# Wireless_Weather_Station.net
KiCad netlist of a schematic drawn in Altium Designer
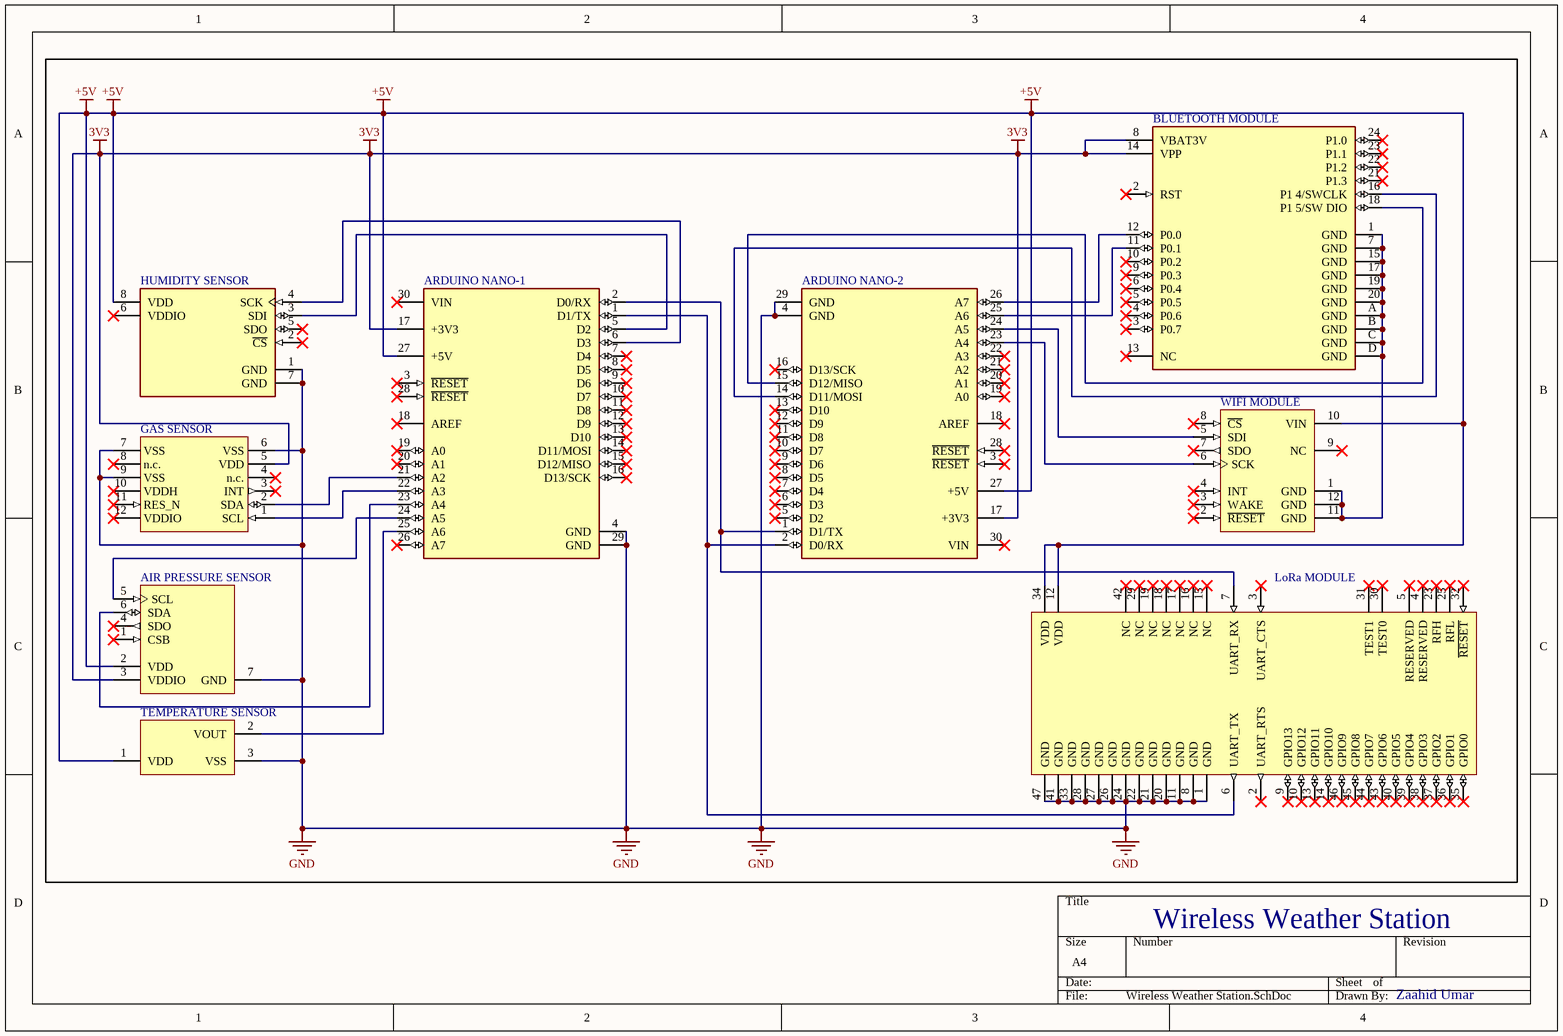
[diagram p0: Wireless Weather Station.SchDoc]

(export (version "E")
  (design (tool "Eeschema 10.0.6"))
  (components
    (comp (ref "AIR PRESSURE SENSOR")
      (value "BMP180")
      (footprint "BOSC-BMP180-7_V")
      (description "Digital Pressure Sensor, 1.8 to 3.6 V, -40 to 85 degC, 7-Pin LGA, RoHS")
      (fields (field (name "MANUFACTURER") "Bosch Sensortec"))
      (libsource (lib "Altium Content Vault") (part "BOSC-BMP180-7"))
    )
    (comp (ref "ARDUINO NANO-1")
      (value "A000005")
      (footprint "FP-A000005-MFG")
      (description "ARDUINO NANO ATMEGA328 EVAL BRD")
      (libsource (lib "Altium Content Vault") (part "d190c066e99afd1c6882cf92e11b2cc"))
    )
    (comp (ref "ARDUINO NANO-2")
      (value "A000005")
      (footprint "FP-A000005-MFG")
      (description "ARDUINO NANO ATMEGA328 EVAL BRD")
      (libsource (lib "") (part "d190c066e99afd1c6882cf92e11b2cc_1"))
    )
    (comp (ref "BLUETOOTH MODULE")
      (value "ENW-89846A1KF")
      (footprint "FP-ENW-89846A1KF-MFG")
      (description "RF TXRX MOD BLUETOOTH CHIP ANT")
      (fields
        (field (name "MANUFACTURER") "Panasonic")
        (field (name "OCTOPART") "https://octopart.com/enw-89846a1kf-panasonic-38566823")
      )
      (libsource (lib "Altium Content Vault") (part "e19c780454142849fd90e01d0101f89"))
    )
    (comp (ref "GAS SENSOR")
      (value "ZMOD4510AI1V")
      (footprint "ZMODxxxx 12 Leads- LGG12")
      (description "ZMOD4510AI1V ZMOD4510 Series 3.6 V 11 mA Gas Sensor Module for Outdoor Air Quality - LGA-12")
      (libsource (lib "Altium Content Vault") (part "ZMOD4510AI1V"))
    )
    (comp (ref "HUMIDITY SENSOR")
      (value "BME280")
      (footprint "FP-BME280-MFG")
      (description "SENSOR PRESSURE HUMIDITY TEMP")
      (libsource (lib "Altium Content Vault") (part "d58e2f6669bc67e6a2bc6a28610ca79"))
    )
    (comp (ref "LoRa MODULE")
      (value "RN2483-I/RM095")
      (footprint "MCHP-RN2483-47_V")
      (fields (field (name "MANUFACTURER") "Microchip"))
      (libsource (lib "Altium Content Vault") (part "MCHP-RN2483-IRM095-47"))
    )
    (comp (ref "TEMPERATURE SENSOR")
      (value "TC1047AVNBTR")
      (footprint "SOT-23-NB3_L")
      (description "Precision Temperature-to-Voltage Converter, 3-Pin SOT-23, Extended Temperature, Tape and Reel")
      (libsource (lib "Altium Content Vault") (part "CON-TVC-TC1046-3"))
    )
    (comp (ref "WIFI MODULE")
      (value "MRF24J40MA-I/RM")
      (footprint "MRF24J40MA")
      (description "2.4 GHz IEEE Std. 802.15.4, RF Transceiver 12-Pin Module, Industrial Temperature")
      (libsource (lib "Altium Content Vault") (part "RF-TRX-MRF24J40-IL12"))
    )
  )
  (nets
    (net (code "1") (name "+5V") (class "Default")
      (node (ref "AIR PRESSURE SENSOR") (pin "2") (pinfunction "VDD_2") (pintype "power_in"))
      (node (ref "ARDUINO NANO-1") (pin "27") (pinfunction "+5V_27") (pintype "power_in"))
      (node (ref "ARDUINO NANO-2") (pin "27") (pinfunction "+5V_27") (pintype "power_in"))
      (node (ref "HUMIDITY SENSOR") (pin "8") (pinfunction "VDD_8") (pintype "power_in"))
      (node (ref "LoRa MODULE") (pin "12") (pinfunction "VDD_12") (pintype "power_in"))
      (node (ref "LoRa MODULE") (pin "34") (pinfunction "VDD_34") (pintype "power_in"))
      (node (ref "TEMPERATURE SENSOR") (pin "1") (pinfunction "VDD_1") (pintype "power_in"))
      (node (ref "WIFI MODULE") (pin "10") (pinfunction "VIN_10") (pintype "power_in"))
    )
    (net (code "2") (name "3V3") (class "Default")
      (node (ref "AIR PRESSURE SENSOR") (pin "3") (pinfunction "VDDIO_3") (pintype "power_in"))
      (node (ref "ARDUINO NANO-1") (pin "17") (pinfunction "+3V3_17") (pintype "power_in"))
      (node (ref "ARDUINO NANO-2") (pin "17") (pinfunction "+3V3_17") (pintype "power_in"))
      (node (ref "BLUETOOTH MODULE") (pin "14") (pinfunction "VPP_14") (pintype "power_in"))
      (node (ref "BLUETOOTH MODULE") (pin "8") (pinfunction "VBAT3V_8") (pintype "power_in"))
      (node (ref "GAS SENSOR") (pin "5") (pinfunction "VDD_5") (pintype "power_in"))
    )
    (net (code "3") (name "GND") (class "Default")
      (node (ref "AIR PRESSURE SENSOR") (pin "7") (pinfunction "GND_7") (pintype "power_in"))
      (node (ref "ARDUINO NANO-1") (pin "29") (pinfunction "GND_29") (pintype "power_in"))
      (node (ref "ARDUINO NANO-1") (pin "4") (pinfunction "GND_4") (pintype "power_in"))
      (node (ref "ARDUINO NANO-2") (pin "29") (pinfunction "GND_29") (pintype "power_in"))
      (node (ref "ARDUINO NANO-2") (pin "4") (pinfunction "GND_4") (pintype "power_in"))
      (node (ref "GAS SENSOR") (pin "6") (pinfunction "VSS_6") (pintype "power_in"))
      (node (ref "GAS SENSOR") (pin "7") (pinfunction "VSS_7") (pintype "power_in"))
      (node (ref "GAS SENSOR") (pin "9") (pinfunction "VSS_9") (pintype "power_in"))
      (node (ref "HUMIDITY SENSOR") (pin "1") (pinfunction "GND_1") (pintype "power_in"))
      (node (ref "HUMIDITY SENSOR") (pin "7") (pinfunction "GND_7") (pintype "power_in"))
      (node (ref "LoRa MODULE") (pin "1") (pinfunction "GND_1") (pintype "power_in"))
      (node (ref "LoRa MODULE") (pin "11") (pinfunction "GND_11") (pintype "power_in"))
      (node (ref "LoRa MODULE") (pin "20") (pinfunction "GND_20") (pintype "power_in"))
      (node (ref "LoRa MODULE") (pin "21") (pinfunction "GND_21") (pintype "power_in"))
      (node (ref "LoRa MODULE") (pin "22") (pinfunction "GND_22") (pintype "power_in"))
      (node (ref "LoRa MODULE") (pin "24") (pinfunction "GND_24") (pintype "power_in"))
      (node (ref "LoRa MODULE") (pin "26") (pinfunction "GND_26") (pintype "power_in"))
      (node (ref "LoRa MODULE") (pin "27") (pinfunction "GND_27") (pintype "power_in"))
      (node (ref "LoRa MODULE") (pin "28") (pinfunction "GND_28") (pintype "power_in"))
      (node (ref "LoRa MODULE") (pin "33") (pinfunction "GND_33") (pintype "power_in"))
      (node (ref "LoRa MODULE") (pin "41") (pinfunction "GND_41") (pintype "power_in"))
      (node (ref "LoRa MODULE") (pin "47") (pinfunction "GND_47") (pintype "power_in"))
      (node (ref "LoRa MODULE") (pin "8") (pinfunction "GND_8") (pintype "power_in"))
      (node (ref "TEMPERATURE SENSOR") (pin "3") (pinfunction "VSS_3") (pintype "power_in"))
    )
    (net (code "4") (name "Net-(AIR PRESSURE SENSOR-SCL)") (class "Default")
      (node (ref "AIR PRESSURE SENSOR") (pin "5") (pinfunction "SCL_5") (pintype "input"))
      (node (ref "ARDUINO NANO-1") (pin "24") (pinfunction "A5_24") (pintype "bidirectional"))
    )
    (net (code "5") (name "Net-(AIR PRESSURE SENSOR-SDA)") (class "Default")
      (node (ref "AIR PRESSURE SENSOR") (pin "6") (pinfunction "SDA_6") (pintype "bidirectional"))
      (node (ref "ARDUINO NANO-1") (pin "23") (pinfunction "A4_23") (pintype "bidirectional"))
    )
    (net (code "6") (name "Net-(ARDUINO NANO-1-A2)") (class "Default")
      (node (ref "ARDUINO NANO-1") (pin "21") (pinfunction "A2_21") (pintype "bidirectional"))
      (node (ref "GAS SENSOR") (pin "2") (pinfunction "SDA_2") (pintype "bidirectional"))
    )
    (net (code "7") (name "Net-(ARDUINO NANO-1-A3)") (class "Default")
      (node (ref "ARDUINO NANO-1") (pin "22") (pinfunction "A3_22") (pintype "bidirectional"))
      (node (ref "GAS SENSOR") (pin "1") (pinfunction "SCL_1") (pintype "input"))
    )
    (net (code "8") (name "Net-(ARDUINO NANO-1-A6)") (class "Default")
      (node (ref "ARDUINO NANO-1") (pin "25") (pinfunction "A6_25") (pintype "bidirectional"))
      (node (ref "TEMPERATURE SENSOR") (pin "2") (pinfunction "VOUT_2") (pintype "power_in"))
    )
    (net (code "9") (name "Net-(ARDUINO NANO-1-D0{slash}RX)") (class "Default")
      (node (ref "ARDUINO NANO-1") (pin "2") (pinfunction "D0/RX_2") (pintype "bidirectional"))
      (node (ref "ARDUINO NANO-2") (pin "1") (pinfunction "D1/TX_1") (pintype "bidirectional"))
      (node (ref "LoRa MODULE") (pin "7") (pinfunction "UART_RX_7") (pintype "input"))
    )
    (net (code "10") (name "Net-(ARDUINO NANO-1-D1{slash}TX)") (class "Default")
      (node (ref "ARDUINO NANO-1") (pin "1") (pinfunction "D1/TX_1") (pintype "bidirectional"))
      (node (ref "ARDUINO NANO-2") (pin "2") (pinfunction "D0/RX_2") (pintype "bidirectional"))
      (node (ref "LoRa MODULE") (pin "6") (pinfunction "UART_TX_6") (pintype "output"))
    )
    (net (code "11") (name "Net-(ARDUINO NANO-1-D2)") (class "Default")
      (node (ref "ARDUINO NANO-1") (pin "5") (pinfunction "D2_5") (pintype "bidirectional"))
      (node (ref "HUMIDITY SENSOR") (pin "3") (pinfunction "SDI_3") (pintype "bidirectional"))
    )
    (net (code "12") (name "Net-(ARDUINO NANO-1-D3)") (class "Default")
      (node (ref "ARDUINO NANO-1") (pin "6") (pinfunction "D3_6") (pintype "bidirectional"))
      (node (ref "HUMIDITY SENSOR") (pin "4") (pinfunction "SCK_4") (pintype "input"))
    )
    (net (code "13") (name "Net-(ARDUINO NANO-2-A4)") (class "Default")
      (node (ref "ARDUINO NANO-2") (pin "23") (pinfunction "A4_23") (pintype "bidirectional"))
      (node (ref "WIFI MODULE") (pin "6") (pinfunction "SCK_6") (pintype "input"))
    )
    (net (code "14") (name "Net-(ARDUINO NANO-2-A5)") (class "Default")
      (node (ref "ARDUINO NANO-2") (pin "24") (pinfunction "A5_24") (pintype "bidirectional"))
      (node (ref "WIFI MODULE") (pin "5") (pinfunction "SDI_5") (pintype "input"))
    )
    (net (code "15") (name "Net-(ARDUINO NANO-2-A6)") (class "Default")
      (node (ref "ARDUINO NANO-2") (pin "25") (pinfunction "A6_25") (pintype "bidirectional"))
      (node (ref "BLUETOOTH MODULE") (pin "11") (pinfunction "P0.1_11") (pintype "bidirectional"))
    )
    (net (code "16") (name "Net-(ARDUINO NANO-2-A7)") (class "Default")
      (node (ref "ARDUINO NANO-2") (pin "26") (pinfunction "A7_26") (pintype "bidirectional"))
      (node (ref "BLUETOOTH MODULE") (pin "12") (pinfunction "P0.0_12") (pintype "bidirectional"))
    )
    (net (code "17") (name "Net-(ARDUINO NANO-2-D11{slash}MOSI)") (class "Default")
      (node (ref "ARDUINO NANO-2") (pin "14") (pinfunction "D11/MOSI_14") (pintype "bidirectional"))
      (node (ref "BLUETOOTH MODULE") (pin "16") (pinfunction "P1_4/SWCLK_16") (pintype "bidirectional"))
    )
    (net (code "18") (name "Net-(ARDUINO NANO-2-D12{slash}MISO)") (class "Default")
      (node (ref "ARDUINO NANO-2") (pin "15") (pinfunction "D12/MISO_15") (pintype "bidirectional"))
      (node (ref "BLUETOOTH MODULE") (pin "18") (pinfunction "P1_5/SW_DIO_18") (pintype "bidirectional"))
    )
    (net (code "19") (name "Net-(BLUETOOTH MODULE-GND-Pad1)") (class "Default")
      (node (ref "BLUETOOTH MODULE") (pin "1") (pinfunction "GND_1") (pintype "power_in"))
      (node (ref "BLUETOOTH MODULE") (pin "15") (pinfunction "GND_15") (pintype "power_in"))
      (node (ref "BLUETOOTH MODULE") (pin "17") (pinfunction "GND_17") (pintype "power_in"))
      (node (ref "BLUETOOTH MODULE") (pin "19") (pinfunction "GND_19") (pintype "power_in"))
      (node (ref "BLUETOOTH MODULE") (pin "20") (pinfunction "GND_20") (pintype "power_in"))
      (node (ref "BLUETOOTH MODULE") (pin "7") (pinfunction "GND_7") (pintype "power_in"))
      (node (ref "BLUETOOTH MODULE") (pin "A") (pinfunction "GND_A") (pintype "power_in"))
      (node (ref "BLUETOOTH MODULE") (pin "B") (pinfunction "GND_B") (pintype "power_in"))
      (node (ref "BLUETOOTH MODULE") (pin "C") (pinfunction "GND_C") (pintype "power_in"))
      (node (ref "BLUETOOTH MODULE") (pin "D") (pinfunction "GND_D") (pintype "power_in"))
      (node (ref "WIFI MODULE") (pin "1") (pinfunction "GND_1") (pintype "power_in"))
      (node (ref "WIFI MODULE") (pin "11") (pinfunction "GND_11") (pintype "power_in"))
      (node (ref "WIFI MODULE") (pin "12") (pinfunction "GND_12") (pintype "power_in"))
    )
    (net (code "20") (name "unconnected-(AIR PRESSURE SENSOR-CSB-Pad1)") (class "Default")
      (node (ref "AIR PRESSURE SENSOR") (pin "1") (pinfunction "CSB_1") (pintype "input+no_connect"))
    )
    (net (code "21") (name "unconnected-(AIR PRESSURE SENSOR-SDO-Pad4)") (class "Default")
      (node (ref "AIR PRESSURE SENSOR") (pin "4") (pinfunction "SDO_4") (pintype "output+no_connect"))
    )
    (net (code "22") (name "unconnected-(ARDUINO NANO-1-A0-Pad19)") (class "Default")
      (node (ref "ARDUINO NANO-1") (pin "19") (pinfunction "A0_19") (pintype "bidirectional+no_connect"))
    )
    (net (code "23") (name "unconnected-(ARDUINO NANO-1-A1-Pad20)") (class "Default")
      (node (ref "ARDUINO NANO-1") (pin "20") (pinfunction "A1_20") (pintype "bidirectional+no_connect"))
    )
    (net (code "24") (name "unconnected-(ARDUINO NANO-1-A7-Pad26)") (class "Default")
      (node (ref "ARDUINO NANO-1") (pin "26") (pinfunction "A7_26") (pintype "bidirectional+no_connect"))
    )
    (net (code "25") (name "unconnected-(ARDUINO NANO-1-AREF-Pad18)") (class "Default")
      (node (ref "ARDUINO NANO-1") (pin "18") (pinfunction "AREF_18") (pintype "passive+no_connect"))
    )
    (net (code "26") (name "unconnected-(ARDUINO NANO-1-D4-Pad7)") (class "Default")
      (node (ref "ARDUINO NANO-1") (pin "7") (pinfunction "D4_7") (pintype "bidirectional+no_connect"))
    )
    (net (code "27") (name "unconnected-(ARDUINO NANO-1-D5-Pad8)") (class "Default")
      (node (ref "ARDUINO NANO-1") (pin "8") (pinfunction "D5_8") (pintype "bidirectional+no_connect"))
    )
    (net (code "28") (name "unconnected-(ARDUINO NANO-1-D6-Pad9)") (class "Default")
      (node (ref "ARDUINO NANO-1") (pin "9") (pinfunction "D6_9") (pintype "bidirectional+no_connect"))
    )
    (net (code "29") (name "unconnected-(ARDUINO NANO-1-D7-Pad10)") (class "Default")
      (node (ref "ARDUINO NANO-1") (pin "10") (pinfunction "D7_10") (pintype "bidirectional+no_connect"))
    )
    (net (code "30") (name "unconnected-(ARDUINO NANO-1-D8-Pad11)") (class "Default")
      (node (ref "ARDUINO NANO-1") (pin "11") (pinfunction "D8_11") (pintype "bidirectional+no_connect"))
    )
    (net (code "31") (name "unconnected-(ARDUINO NANO-1-D9-Pad12)") (class "Default")
      (node (ref "ARDUINO NANO-1") (pin "12") (pinfunction "D9_12") (pintype "bidirectional+no_connect"))
    )
    (net (code "32") (name "unconnected-(ARDUINO NANO-1-D10-Pad13)") (class "Default")
      (node (ref "ARDUINO NANO-1") (pin "13") (pinfunction "D10_13") (pintype "bidirectional+no_connect"))
    )
    (net (code "33") (name "unconnected-(ARDUINO NANO-1-D11{slash}MOSI-Pad14)") (class "Default")
      (node (ref "ARDUINO NANO-1") (pin "14") (pinfunction "D11/MOSI_14") (pintype "bidirectional+no_connect"))
    )
    (net (code "34") (name "unconnected-(ARDUINO NANO-1-D12{slash}MISO-Pad15)") (class "Default")
      (node (ref "ARDUINO NANO-1") (pin "15") (pinfunction "D12/MISO_15") (pintype "bidirectional+no_connect"))
    )
    (net (code "35") (name "unconnected-(ARDUINO NANO-1-D13{slash}SCK-Pad16)") (class "Default")
      (node (ref "ARDUINO NANO-1") (pin "16") (pinfunction "D13/SCK_16") (pintype "bidirectional+no_connect"))
    )
    (net (code "36") (name "unconnected-(ARDUINO NANO-1-VIN-Pad30)") (class "Default")
      (node (ref "ARDUINO NANO-1") (pin "30") (pinfunction "VIN_30") (pintype "power_in+no_connect"))
    )
    (net (code "37") (name "unconnected-(ARDUINO NANO-1-~{RESET}-Pad3)") (class "Default")
      (node (ref "ARDUINO NANO-1") (pin "3") (pinfunction "~{RESET}_3") (pintype "input+no_connect"))
    )
    (net (code "38") (name "unconnected-(ARDUINO NANO-1-~{RESET}-Pad28)") (class "Default")
      (node (ref "ARDUINO NANO-1") (pin "28") (pinfunction "~{RESET}_28") (pintype "input+no_connect"))
    )
    (net (code "39") (name "unconnected-(ARDUINO NANO-2-A0-Pad19)") (class "Default")
      (node (ref "ARDUINO NANO-2") (pin "19") (pinfunction "A0_19") (pintype "bidirectional+no_connect"))
    )
    (net (code "40") (name "unconnected-(ARDUINO NANO-2-A1-Pad20)") (class "Default")
      (node (ref "ARDUINO NANO-2") (pin "20") (pinfunction "A1_20") (pintype "bidirectional+no_connect"))
    )
    (net (code "41") (name "unconnected-(ARDUINO NANO-2-A2-Pad21)") (class "Default")
      (node (ref "ARDUINO NANO-2") (pin "21") (pinfunction "A2_21") (pintype "bidirectional+no_connect"))
    )
    (net (code "42") (name "unconnected-(ARDUINO NANO-2-A3-Pad22)") (class "Default")
      (node (ref "ARDUINO NANO-2") (pin "22") (pinfunction "A3_22") (pintype "bidirectional+no_connect"))
    )
    (net (code "43") (name "unconnected-(ARDUINO NANO-2-AREF-Pad18)") (class "Default")
      (node (ref "ARDUINO NANO-2") (pin "18") (pinfunction "AREF_18") (pintype "passive+no_connect"))
    )
    (net (code "44") (name "unconnected-(ARDUINO NANO-2-D2-Pad5)") (class "Default")
      (node (ref "ARDUINO NANO-2") (pin "5") (pinfunction "D2_5") (pintype "bidirectional+no_connect"))
    )
    (net (code "45") (name "unconnected-(ARDUINO NANO-2-D3-Pad6)") (class "Default")
      (node (ref "ARDUINO NANO-2") (pin "6") (pinfunction "D3_6") (pintype "bidirectional+no_connect"))
    )
    (net (code "46") (name "unconnected-(ARDUINO NANO-2-D4-Pad7)") (class "Default")
      (node (ref "ARDUINO NANO-2") (pin "7") (pinfunction "D4_7") (pintype "bidirectional+no_connect"))
    )
    (net (code "47") (name "unconnected-(ARDUINO NANO-2-D5-Pad8)") (class "Default")
      (node (ref "ARDUINO NANO-2") (pin "8") (pinfunction "D5_8") (pintype "bidirectional+no_connect"))
    )
    (net (code "48") (name "unconnected-(ARDUINO NANO-2-D6-Pad9)") (class "Default")
      (node (ref "ARDUINO NANO-2") (pin "9") (pinfunction "D6_9") (pintype "bidirectional+no_connect"))
    )
    (net (code "49") (name "unconnected-(ARDUINO NANO-2-D7-Pad10)") (class "Default")
      (node (ref "ARDUINO NANO-2") (pin "10") (pinfunction "D7_10") (pintype "bidirectional+no_connect"))
    )
    (net (code "50") (name "unconnected-(ARDUINO NANO-2-D8-Pad11)") (class "Default")
      (node (ref "ARDUINO NANO-2") (pin "11") (pinfunction "D8_11") (pintype "bidirectional+no_connect"))
    )
    (net (code "51") (name "unconnected-(ARDUINO NANO-2-D9-Pad12)") (class "Default")
      (node (ref "ARDUINO NANO-2") (pin "12") (pinfunction "D9_12") (pintype "bidirectional+no_connect"))
    )
    (net (code "52") (name "unconnected-(ARDUINO NANO-2-D10-Pad13)") (class "Default")
      (node (ref "ARDUINO NANO-2") (pin "13") (pinfunction "D10_13") (pintype "bidirectional+no_connect"))
    )
    (net (code "53") (name "unconnected-(ARDUINO NANO-2-D13{slash}SCK-Pad16)") (class "Default")
      (node (ref "ARDUINO NANO-2") (pin "16") (pinfunction "D13/SCK_16") (pintype "bidirectional+no_connect"))
    )
    (net (code "54") (name "unconnected-(ARDUINO NANO-2-VIN-Pad30)") (class "Default")
      (node (ref "ARDUINO NANO-2") (pin "30") (pinfunction "VIN_30") (pintype "power_in+no_connect"))
    )
    (net (code "55") (name "unconnected-(ARDUINO NANO-2-~{RESET}-Pad3)") (class "Default")
      (node (ref "ARDUINO NANO-2") (pin "3") (pinfunction "~{RESET}_3") (pintype "input+no_connect"))
    )
    (net (code "56") (name "unconnected-(ARDUINO NANO-2-~{RESET}-Pad28)") (class "Default")
      (node (ref "ARDUINO NANO-2") (pin "28") (pinfunction "~{RESET}_28") (pintype "input+no_connect"))
    )
    (net (code "57") (name "unconnected-(BLUETOOTH MODULE-NC-Pad13)") (class "Default")
      (node (ref "BLUETOOTH MODULE") (pin "13") (pinfunction "NC_13") (pintype "passive+no_connect"))
    )
    (net (code "58") (name "unconnected-(BLUETOOTH MODULE-P0.2-Pad10)") (class "Default")
      (node (ref "BLUETOOTH MODULE") (pin "10") (pinfunction "P0.2_10") (pintype "bidirectional+no_connect"))
    )
    (net (code "59") (name "unconnected-(BLUETOOTH MODULE-P0.3-Pad9)") (class "Default")
      (node (ref "BLUETOOTH MODULE") (pin "9") (pinfunction "P0.3_9") (pintype "bidirectional+no_connect"))
    )
    (net (code "60") (name "unconnected-(BLUETOOTH MODULE-P0.4-Pad6)") (class "Default")
      (node (ref "BLUETOOTH MODULE") (pin "6") (pinfunction "P0.4_6") (pintype "bidirectional+no_connect"))
    )
    (net (code "61") (name "unconnected-(BLUETOOTH MODULE-P0.5-Pad5)") (class "Default")
      (node (ref "BLUETOOTH MODULE") (pin "5") (pinfunction "P0.5_5") (pintype "bidirectional+no_connect"))
    )
    (net (code "62") (name "unconnected-(BLUETOOTH MODULE-P0.6-Pad4)") (class "Default")
      (node (ref "BLUETOOTH MODULE") (pin "4") (pinfunction "P0.6_4") (pintype "bidirectional+no_connect"))
    )
    (net (code "63") (name "unconnected-(BLUETOOTH MODULE-P0.7-Pad3)") (class "Default")
      (node (ref "BLUETOOTH MODULE") (pin "3") (pinfunction "P0.7_3") (pintype "bidirectional+no_connect"))
    )
    (net (code "64") (name "unconnected-(BLUETOOTH MODULE-P1.0-Pad24)") (class "Default")
      (node (ref "BLUETOOTH MODULE") (pin "24") (pinfunction "P1.0_24") (pintype "bidirectional+no_connect"))
    )
    (net (code "65") (name "unconnected-(BLUETOOTH MODULE-P1.1-Pad23)") (class "Default")
      (node (ref "BLUETOOTH MODULE") (pin "23") (pinfunction "P1.1_23") (pintype "bidirectional+no_connect"))
    )
    (net (code "66") (name "unconnected-(BLUETOOTH MODULE-P1.2-Pad22)") (class "Default")
      (node (ref "BLUETOOTH MODULE") (pin "22") (pinfunction "P1.2_22") (pintype "bidirectional+no_connect"))
    )
    (net (code "67") (name "unconnected-(BLUETOOTH MODULE-P1.3-Pad21)") (class "Default")
      (node (ref "BLUETOOTH MODULE") (pin "21") (pinfunction "P1.3_21") (pintype "bidirectional+no_connect"))
    )
    (net (code "68") (name "unconnected-(BLUETOOTH MODULE-RST-Pad2)") (class "Default")
      (node (ref "BLUETOOTH MODULE") (pin "2") (pinfunction "RST_2") (pintype "input+no_connect"))
    )
    (net (code "69") (name "unconnected-(GAS SENSOR-INT-Pad3)") (class "Default")
      (node (ref "GAS SENSOR") (pin "3") (pinfunction "INT_3") (pintype "output+no_connect"))
    )
    (net (code "70") (name "unconnected-(GAS SENSOR-RES_N-Pad11)") (class "Default")
      (node (ref "GAS SENSOR") (pin "11") (pinfunction "RES_N_11") (pintype "input+no_connect"))
    )
    (net (code "71") (name "unconnected-(GAS SENSOR-VDDH-Pad10)") (class "Default")
      (node (ref "GAS SENSOR") (pin "10") (pinfunction "VDDH_10") (pintype "power_in+no_connect"))
    )
    (net (code "72") (name "unconnected-(GAS SENSOR-VDDIO-Pad12)") (class "Default")
      (node (ref "GAS SENSOR") (pin "12") (pinfunction "VDDIO_12") (pintype "power_in+no_connect"))
    )
    (net (code "73") (name "unconnected-(GAS SENSOR-n.c.-Pad4)") (class "Default")
      (node (ref "GAS SENSOR") (pin "4") (pinfunction "n.c._4") (pintype "passive+no_connect"))
    )
    (net (code "74") (name "unconnected-(GAS SENSOR-n.c.-Pad8)") (class "Default")
      (node (ref "GAS SENSOR") (pin "8") (pinfunction "n.c._8") (pintype "passive+no_connect"))
    )
    (net (code "75") (name "unconnected-(HUMIDITY SENSOR-SDO-Pad5)") (class "Default")
      (node (ref "HUMIDITY SENSOR") (pin "5") (pinfunction "SDO_5") (pintype "bidirectional+no_connect"))
    )
    (net (code "76") (name "unconnected-(HUMIDITY SENSOR-VDDIO-Pad6)") (class "Default")
      (node (ref "HUMIDITY SENSOR") (pin "6") (pinfunction "VDDIO_6") (pintype "power_in+no_connect"))
    )
    (net (code "77") (name "unconnected-(HUMIDITY SENSOR-~{CS}-Pad2)") (class "Default")
      (node (ref "HUMIDITY SENSOR") (pin "2") (pinfunction "~{CS}_2") (pintype "input+no_connect"))
    )
    (net (code "78") (name "unconnected-(LoRa MODULE-GPIO0-Pad35)") (class "Default")
      (node (ref "LoRa MODULE") (pin "35") (pinfunction "GPIO0_35") (pintype "bidirectional+no_connect"))
    )
    (net (code "79") (name "unconnected-(LoRa MODULE-GPIO1-Pad36)") (class "Default")
      (node (ref "LoRa MODULE") (pin "36") (pinfunction "GPIO1_36") (pintype "bidirectional+no_connect"))
    )
    (net (code "80") (name "unconnected-(LoRa MODULE-GPIO2-Pad37)") (class "Default")
      (node (ref "LoRa MODULE") (pin "37") (pinfunction "GPIO2_37") (pintype "bidirectional+no_connect"))
    )
    (net (code "81") (name "unconnected-(LoRa MODULE-GPIO3-Pad38)") (class "Default")
      (node (ref "LoRa MODULE") (pin "38") (pinfunction "GPIO3_38") (pintype "bidirectional+no_connect"))
    )
    (net (code "82") (name "unconnected-(LoRa MODULE-GPIO4-Pad39)") (class "Default")
      (node (ref "LoRa MODULE") (pin "39") (pinfunction "GPIO4_39") (pintype "bidirectional+no_connect"))
    )
    (net (code "83") (name "unconnected-(LoRa MODULE-GPIO5-Pad40)") (class "Default")
      (node (ref "LoRa MODULE") (pin "40") (pinfunction "GPIO5_40") (pintype "bidirectional+no_connect"))
    )
    (net (code "84") (name "unconnected-(LoRa MODULE-GPIO6-Pad43)") (class "Default")
      (node (ref "LoRa MODULE") (pin "43") (pinfunction "GPIO6_43") (pintype "bidirectional+no_connect"))
    )
    (net (code "85") (name "unconnected-(LoRa MODULE-GPIO7-Pad44)") (class "Default")
      (node (ref "LoRa MODULE") (pin "44") (pinfunction "GPIO7_44") (pintype "bidirectional+no_connect"))
    )
    (net (code "86") (name "unconnected-(LoRa MODULE-GPIO8-Pad45)") (class "Default")
      (node (ref "LoRa MODULE") (pin "45") (pinfunction "GPIO8_45") (pintype "bidirectional+no_connect"))
    )
    (net (code "87") (name "unconnected-(LoRa MODULE-GPIO9-Pad46)") (class "Default")
      (node (ref "LoRa MODULE") (pin "46") (pinfunction "GPIO9_46") (pintype "bidirectional+no_connect"))
    )
    (net (code "88") (name "unconnected-(LoRa MODULE-GPIO10-Pad14)") (class "Default")
      (node (ref "LoRa MODULE") (pin "14") (pinfunction "GPIO10_14") (pintype "bidirectional+no_connect"))
    )
    (net (code "89") (name "unconnected-(LoRa MODULE-GPIO11-Pad13)") (class "Default")
      (node (ref "LoRa MODULE") (pin "13") (pinfunction "GPIO11_13") (pintype "bidirectional+no_connect"))
    )
    (net (code "90") (name "unconnected-(LoRa MODULE-GPIO12-Pad10)") (class "Default")
      (node (ref "LoRa MODULE") (pin "10") (pinfunction "GPIO12_10") (pintype "bidirectional+no_connect"))
    )
    (net (code "91") (name "unconnected-(LoRa MODULE-GPIO13-Pad9)") (class "Default")
      (node (ref "LoRa MODULE") (pin "9") (pinfunction "GPIO13_9") (pintype "bidirectional+no_connect"))
    )
    (net (code "92") (name "unconnected-(LoRa MODULE-NC-Pad15)") (class "Default")
      (node (ref "LoRa MODULE") (pin "15") (pinfunction "NC_15") (pintype "passive+no_connect"))
    )
    (net (code "93") (name "unconnected-(LoRa MODULE-NC-Pad16)") (class "Default")
      (node (ref "LoRa MODULE") (pin "16") (pinfunction "NC_16") (pintype "passive+no_connect"))
    )
    (net (code "94") (name "unconnected-(LoRa MODULE-NC-Pad17)") (class "Default")
      (node (ref "LoRa MODULE") (pin "17") (pinfunction "NC_17") (pintype "passive+no_connect"))
    )
    (net (code "95") (name "unconnected-(LoRa MODULE-NC-Pad18)") (class "Default")
      (node (ref "LoRa MODULE") (pin "18") (pinfunction "NC_18") (pintype "passive+no_connect"))
    )
    (net (code "96") (name "unconnected-(LoRa MODULE-NC-Pad19)") (class "Default")
      (node (ref "LoRa MODULE") (pin "19") (pinfunction "NC_19") (pintype "passive+no_connect"))
    )
    (net (code "97") (name "unconnected-(LoRa MODULE-NC-Pad29)") (class "Default")
      (node (ref "LoRa MODULE") (pin "29") (pinfunction "NC_29") (pintype "passive+no_connect"))
    )
    (net (code "98") (name "unconnected-(LoRa MODULE-NC-Pad42)") (class "Default")
      (node (ref "LoRa MODULE") (pin "42") (pinfunction "NC_42") (pintype "passive+no_connect"))
    )
    (net (code "99") (name "unconnected-(LoRa MODULE-RESERVED-Pad4)") (class "Default")
      (node (ref "LoRa MODULE") (pin "4") (pinfunction "RESERVED_4") (pintype "passive+no_connect"))
    )
    (net (code "100") (name "unconnected-(LoRa MODULE-RESERVED-Pad5)") (class "Default")
      (node (ref "LoRa MODULE") (pin "5") (pinfunction "RESERVED_5") (pintype "passive+no_connect"))
    )
    (net (code "101") (name "unconnected-(LoRa MODULE-RFH-Pad23)") (class "Default")
      (node (ref "LoRa MODULE") (pin "23") (pinfunction "RFH_23") (pintype "passive+no_connect"))
    )
    (net (code "102") (name "unconnected-(LoRa MODULE-RFL-Pad25)") (class "Default")
      (node (ref "LoRa MODULE") (pin "25") (pinfunction "RFL_25") (pintype "passive+no_connect"))
    )
    (net (code "103") (name "unconnected-(LoRa MODULE-TEST0-Pad30)") (class "Default")
      (node (ref "LoRa MODULE") (pin "30") (pinfunction "TEST0_30") (pintype "passive+no_connect"))
    )
    (net (code "104") (name "unconnected-(LoRa MODULE-TEST1-Pad31)") (class "Default")
      (node (ref "LoRa MODULE") (pin "31") (pinfunction "TEST1_31") (pintype "passive+no_connect"))
    )
    (net (code "105") (name "unconnected-(LoRa MODULE-UART_CTS-Pad3)") (class "Default")
      (node (ref "LoRa MODULE") (pin "3") (pinfunction "UART_CTS_3") (pintype "input+no_connect"))
    )
    (net (code "106") (name "unconnected-(LoRa MODULE-UART_RTS-Pad2)") (class "Default")
      (node (ref "LoRa MODULE") (pin "2") (pinfunction "UART_RTS_2") (pintype "output+no_connect"))
    )
    (net (code "107") (name "unconnected-(LoRa MODULE-~{RESET}-Pad32)") (class "Default")
      (node (ref "LoRa MODULE") (pin "32") (pinfunction "~{RESET}_32") (pintype "input+no_connect"))
    )
    (net (code "108") (name "unconnected-(WIFI MODULE-INT-Pad4)") (class "Default")
      (node (ref "WIFI MODULE") (pin "4") (pinfunction "INT_4") (pintype "input+no_connect"))
    )
    (net (code "109") (name "unconnected-(WIFI MODULE-NC-Pad9)") (class "Default")
      (node (ref "WIFI MODULE") (pin "9") (pinfunction "NC_9") (pintype "passive+no_connect"))
    )
    (net (code "110") (name "unconnected-(WIFI MODULE-SDO-Pad7)") (class "Default")
      (node (ref "WIFI MODULE") (pin "7") (pinfunction "SDO_7") (pintype "output+no_connect"))
    )
    (net (code "111") (name "unconnected-(WIFI MODULE-WAKE-Pad3)") (class "Default")
      (node (ref "WIFI MODULE") (pin "3") (pinfunction "WAKE_3") (pintype "input+no_connect"))
    )
    (net (code "112") (name "unconnected-(WIFI MODULE-~{CS}-Pad8)") (class "Default")
      (node (ref "WIFI MODULE") (pin "8") (pinfunction "~{CS}_8") (pintype "input+no_connect"))
    )
    (net (code "113") (name "unconnected-(WIFI MODULE-~{RESET}-Pad2)") (class "Default")
      (node (ref "WIFI MODULE") (pin "2") (pinfunction "~{RESET}_2") (pintype "input+no_connect"))
    )
  )
)
